# design.net
KiCad netlist of a schematic drawn in Altium Designer
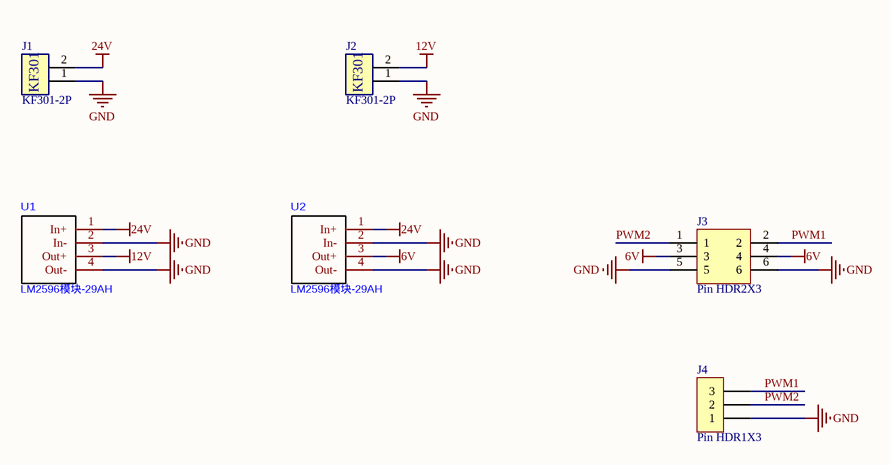
[diagram p0: 电源.SchDoc]

(export (version "E")
  (design (tool "Eeschema 10.0.6"))
  (components
    (comp (ref "J1")
      (value "KF301-2P")
      (footprint "KF301-5.0-2P")
      (libsource (lib "KF301") (part "KF301-2P"))
    )
    (comp (ref "J2")
      (value "KF301-2P")
      (footprint "KF301-5.0-2P")
      (libsource (lib "KF301") (part "KF301-2P"))
    )
    (comp (ref "J3")
      (value "Pin HDR2X3")
      (footprint "Pin HDR2X3/2.54mm-S")
      (libsource (lib "排针") (part "Pin HDR2X3"))
    )
    (comp (ref "J4")
      (value "Pin HDR1X3")
      (footprint "Pin HDR1X3/2.54mm-S")
      (libsource (lib "排针") (part "Pin HDR1X3"))
    )
    (comp (ref "U1")
      (value "LM2596模块-29AH")
      (footprint "LM2596")
      (libsource (lib "zy lib") (part "LM2596模块-29AH"))
    )
    (comp (ref "U2")
      (value "LM2596模块-29AH")
      (footprint "LM2596")
      (libsource (lib "zy lib") (part "LM2596模块-29AH"))
    )
  )
  (nets
    (net (code "1") (name "/PWM1") (class "Default")
      (node (ref "J3") (pin "2") (pinfunction "2_2") (pintype "passive"))
      (node (ref "J4") (pin "3") (pinfunction "3_3") (pintype "passive"))
    )
    (net (code "2") (name "/PWM2") (class "Default")
      (node (ref "J3") (pin "1") (pinfunction "1_1") (pintype "passive"))
      (node (ref "J4") (pin "2") (pinfunction "2_2") (pintype "passive"))
    )
    (net (code "3") (name "6V") (class "Default")
      (node (ref "J3") (pin "3") (pinfunction "3_3") (pintype "passive"))
      (node (ref "J3") (pin "4") (pinfunction "4_4") (pintype "passive"))
      (node (ref "U2") (pin "3") (pinfunction "Out+_3") (pintype "passive"))
    )
    (net (code "4") (name "12V") (class "Default")
      (node (ref "J2") (pin "2") (pinfunction "2_2") (pintype "passive"))
      (node (ref "U1") (pin "3") (pinfunction "Out+_3") (pintype "passive"))
    )
    (net (code "5") (name "24V") (class "Default")
      (node (ref "J1") (pin "2") (pinfunction "2_2") (pintype "passive"))
      (node (ref "U1") (pin "1") (pinfunction "In+_1") (pintype "passive"))
      (node (ref "U2") (pin "1") (pinfunction "In+_1") (pintype "passive"))
    )
    (net (code "6") (name "GND") (class "Default")
      (node (ref "J1") (pin "1") (pinfunction "1_1") (pintype "passive"))
      (node (ref "J2") (pin "1") (pinfunction "1_1") (pintype "passive"))
      (node (ref "J3") (pin "5") (pinfunction "5_5") (pintype "passive"))
      (node (ref "J3") (pin "6") (pinfunction "6_6") (pintype "passive"))
      (node (ref "J4") (pin "1") (pinfunction "1_1") (pintype "passive"))
      (node (ref "U1") (pin "2") (pinfunction "In-_2") (pintype "passive"))
      (node (ref "U1") (pin "4") (pinfunction "Out-_4") (pintype "passive"))
      (node (ref "U2") (pin "2") (pinfunction "In-_2") (pintype "passive"))
      (node (ref "U2") (pin "4") (pinfunction "Out-_4") (pintype "passive"))
    )
  )
)
